# esp32_wheel_robot.net
KiCad netlist of a schematic drawn in EasyEDA Pro
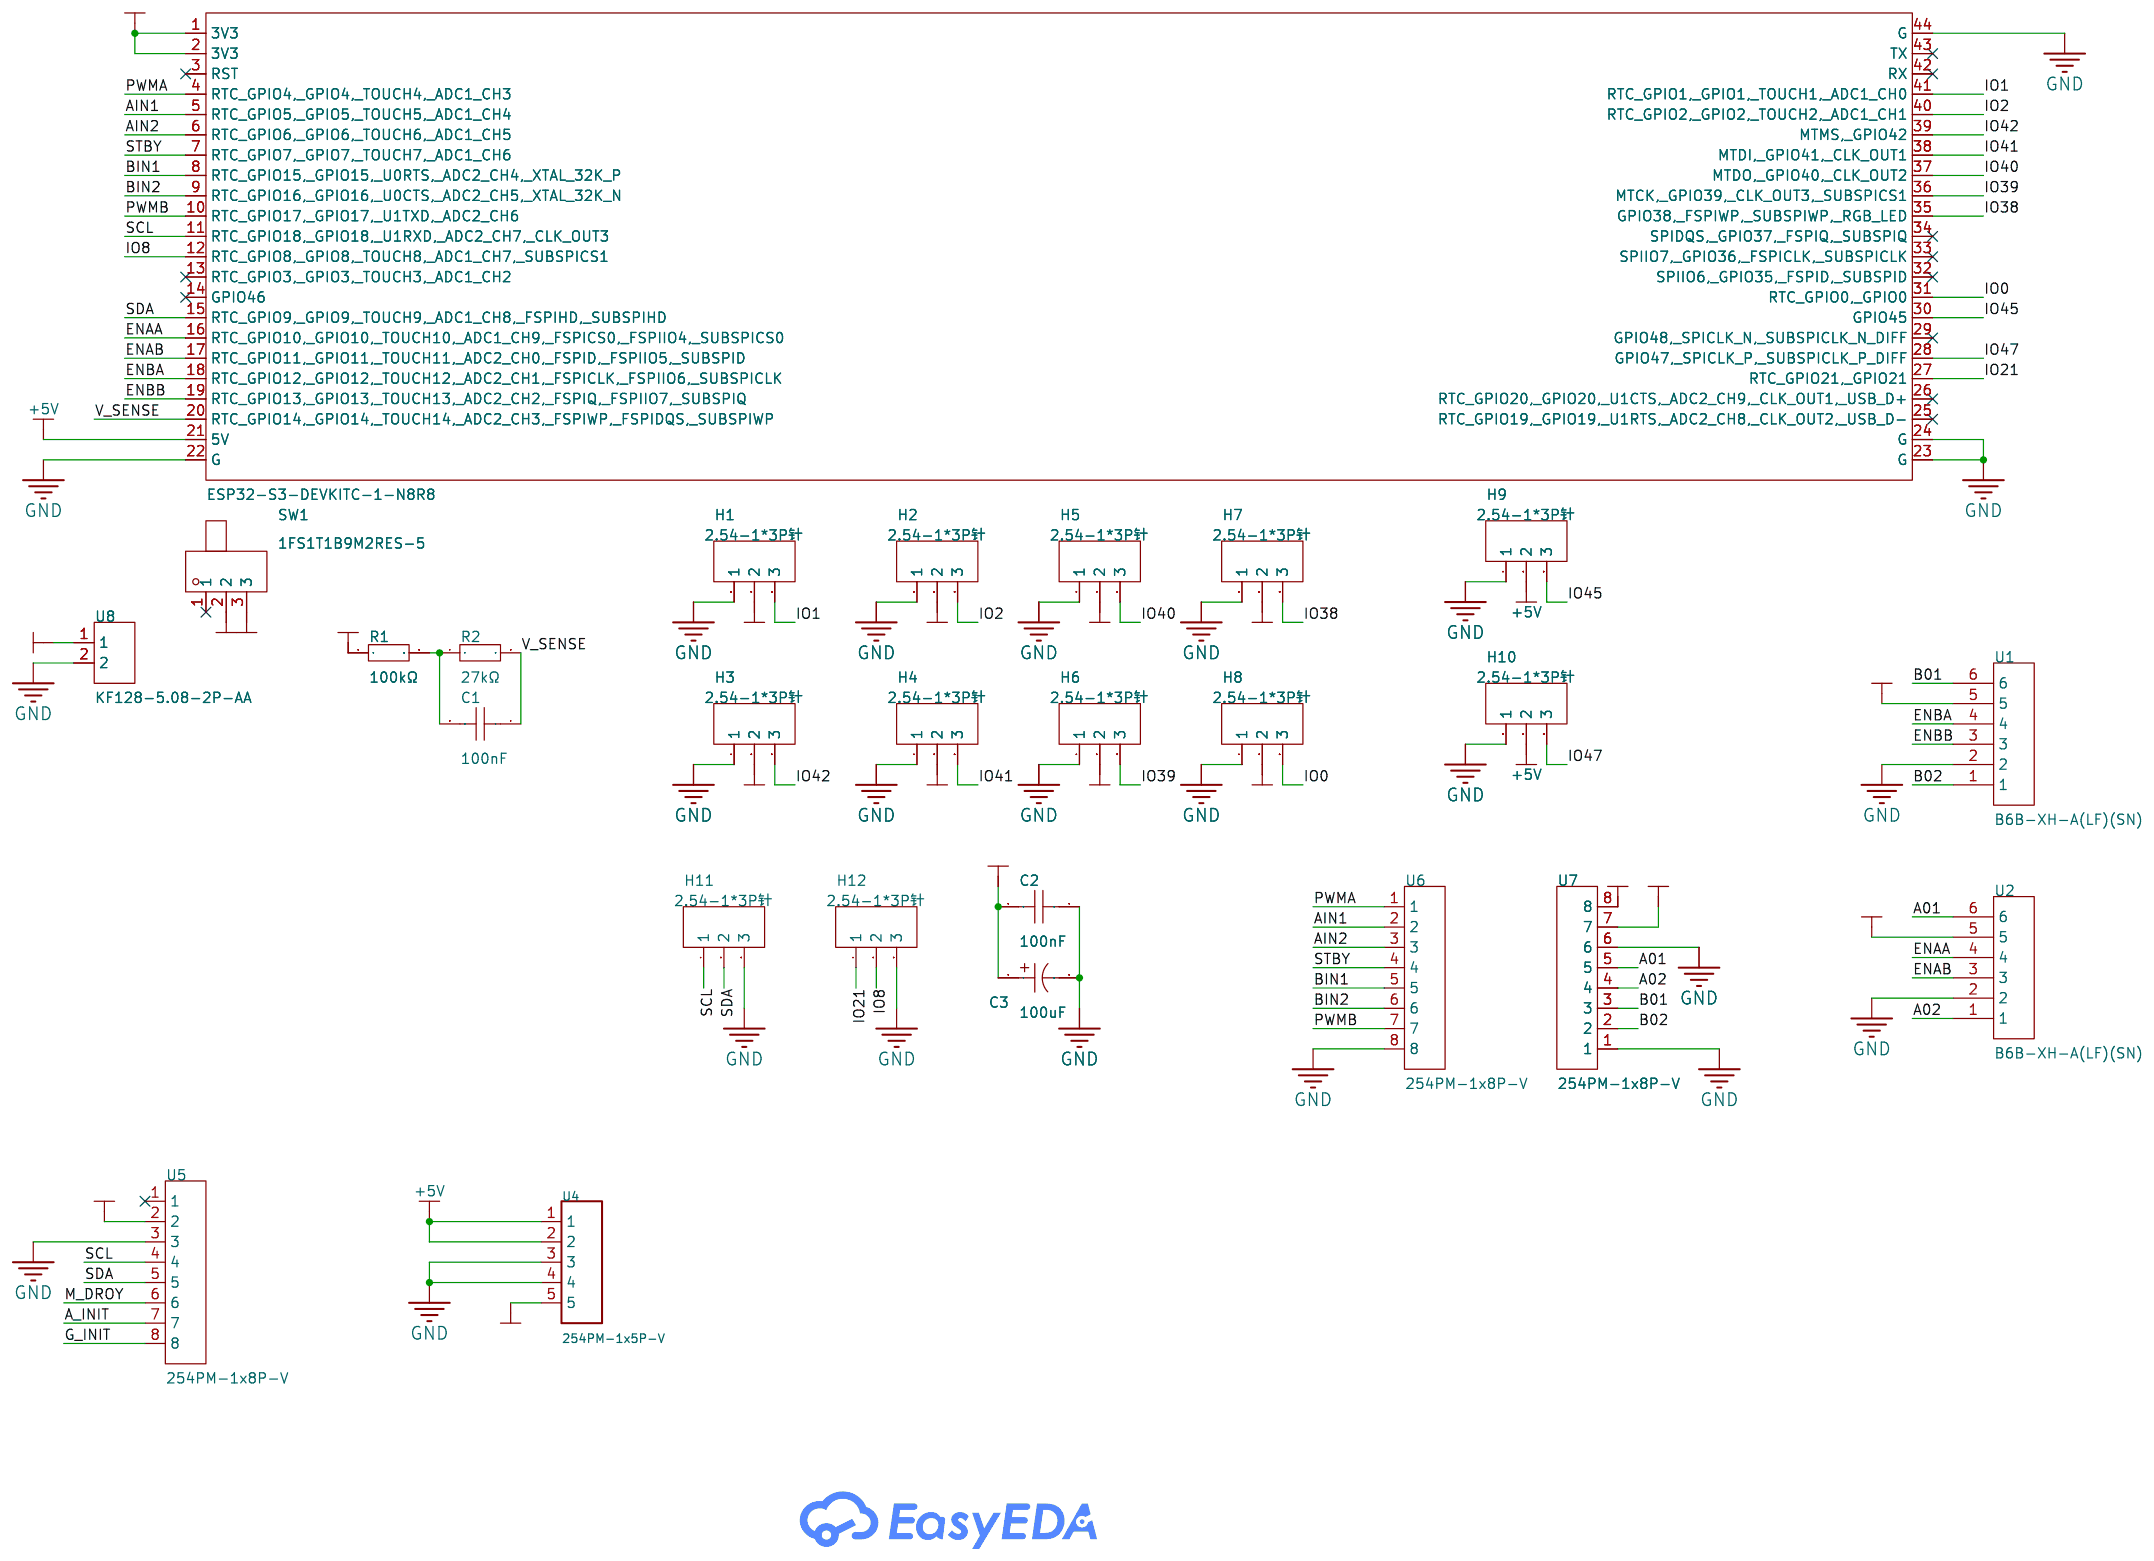
[diagram p0: schematic sheet]

(export (version "E")
  (design (tool "Eeschema 10.0.6"))
  (components
    (comp (ref "C1")
      (value "100nF")
      (footprint "easyedapro:C0603")
      (fields
        (field (name "Manufacturer Part") "CC1H104MC1FD3F6C10MF")
        (field (name "Manufacturer") "Dersonic(德尔创)")
      )
      (libsource (lib "easyedapro") (part "CAP_OLD"))
    )
    (comp (ref "C2")
      (value "100nF")
      (footprint "easyedapro:C0603")
      (fields
        (field (name "Manufacturer Part") "CC1H104MC1FD3F6C10MF")
        (field (name "Manufacturer") "Dersonic(德尔创)")
      )
      (libsource (lib "easyedapro") (part "CAP_OLD"))
    )
    (comp (ref "C3")
      (value "100uF")
      (footprint "easyedapro:CAP-TH_BD10.0-P5.00-D0.8-FD_UKZ1E101MPM1TD")
      (fields
        (field (name "Manufacturer Part") "UKZ1E101MPM1TD")
        (field (name "Manufacturer") "Nichicon(尼吉康)")
      )
      (libsource (lib "easyedapro") (part "UKZ1E101MPM1TD"))
    )
    (comp (ref "H1")
      (value "2.54-1*3P针")
      (footprint "easyedapro:HDR-TH_3P-P2.54-V-M-1")
      (fields (field (name "Manufacturer") "BOOMELE(博穆精密)"))
      (libsource (lib "easyedapro") (part "Header-Male-2.54_1x3"))
    )
    (comp (ref "H2")
      (value "2.54-1*3P针")
      (footprint "easyedapro:HDR-TH_3P-P2.54-V-M-1")
      (fields (field (name "Manufacturer") "BOOMELE(博穆精密)"))
      (libsource (lib "easyedapro") (part "Header-Male-2.54_1x3"))
    )
    (comp (ref "H3")
      (value "2.54-1*3P针")
      (footprint "easyedapro:HDR-TH_3P-P2.54-V-M-1")
      (fields (field (name "Manufacturer") "BOOMELE(博穆精密)"))
      (libsource (lib "easyedapro") (part "Header-Male-2.54_1x3"))
    )
    (comp (ref "H4")
      (value "2.54-1*3P针")
      (footprint "easyedapro:HDR-TH_3P-P2.54-V-M-1")
      (fields (field (name "Manufacturer") "BOOMELE(博穆精密)"))
      (libsource (lib "easyedapro") (part "Header-Male-2.54_1x3"))
    )
    (comp (ref "H5")
      (value "2.54-1*3P针")
      (footprint "easyedapro:HDR-TH_3P-P2.54-V-M-1")
      (fields (field (name "Manufacturer") "BOOMELE(博穆精密)"))
      (libsource (lib "easyedapro") (part "Header-Male-2.54_1x3"))
    )
    (comp (ref "H6")
      (value "2.54-1*3P针")
      (footprint "easyedapro:HDR-TH_3P-P2.54-V-M-1")
      (fields (field (name "Manufacturer") "BOOMELE(博穆精密)"))
      (libsource (lib "easyedapro") (part "Header-Male-2.54_1x3"))
    )
    (comp (ref "H7")
      (value "2.54-1*3P针")
      (footprint "easyedapro:HDR-TH_3P-P2.54-V-M-1")
      (fields (field (name "Manufacturer") "BOOMELE(博穆精密)"))
      (libsource (lib "easyedapro") (part "Header-Male-2.54_1x3"))
    )
    (comp (ref "H8")
      (value "2.54-1*3P针")
      (footprint "easyedapro:HDR-TH_3P-P2.54-V-M-1")
      (fields (field (name "Manufacturer") "BOOMELE(博穆精密)"))
      (libsource (lib "easyedapro") (part "Header-Male-2.54_1x3"))
    )
    (comp (ref "H9")
      (value "2.54-1*3P针")
      (footprint "easyedapro:HDR-TH_3P-P2.54-V-M-1")
      (fields (field (name "Manufacturer") "BOOMELE(博穆精密)"))
      (libsource (lib "easyedapro") (part "Header-Male-2.54_1x3"))
    )
    (comp (ref "H10")
      (value "2.54-1*3P针")
      (footprint "easyedapro:HDR-TH_3P-P2.54-V-M-1")
      (fields (field (name "Manufacturer") "BOOMELE(博穆精密)"))
      (libsource (lib "easyedapro") (part "Header-Male-2.54_1x3"))
    )
    (comp (ref "H11")
      (value "2.54-1*3P针")
      (footprint "easyedapro:HDR-TH_3P-P2.54-V-M-1")
      (fields (field (name "Manufacturer") "BOOMELE(博穆精密)"))
      (libsource (lib "easyedapro") (part "Header-Male-2.54_1x3"))
    )
    (comp (ref "H12")
      (value "2.54-1*3P针")
      (footprint "easyedapro:HDR-TH_3P-P2.54-V-M-1")
      (fields (field (name "Manufacturer") "BOOMELE(博穆精密)"))
      (libsource (lib "easyedapro") (part "Header-Male-2.54_1x3"))
    )
    (comp (ref "R1")
      (value "100kΩ")
      (footprint "easyedapro:R0603")
      (fields
        (field (name "Manufacturer Part") "MF1/4W-100KΩ±1% T")
        (field (name "Manufacturer") "CCO(千志电子)")
      )
      (libsource (lib "easyedapro") (part "Res"))
    )
    (comp (ref "R2")
      (value "27kΩ")
      (footprint "easyedapro:R0603")
      (fields (field (name "Manufacturer Part") "MF1/4W-27KΩ±1% T") (field (name "Manufacturer") "CCO(千志电子)"))
      (libsource (lib "easyedapro") (part "Res"))
    )
    (comp (ref "SW1")
      (value "1FS1T1B9M2RES-5")
      (footprint "easyedapro:SW-TH_1FS1T1B9M2RES-5")
      (fields (field (name "Manufacturer") "Dailywell(德利威)"))
      (libsource (lib "easyedapro") (part "1FS1T1B9M2RES-5"))
    )
    (comp (ref "U1")
      (value "B6B-XH-A(LF)(SN)")
      (footprint "easyedapro:CONN-TH_6P-P2.50_B6B-XH-A-LF-SN")
      (fields (field (name "Manufacturer") "JST"))
      (libsource (lib "easyedapro") (part "B6B-XH-A(LF)(SN)"))
    )
    (comp (ref "U2")
      (value "B6B-XH-A(LF)(SN)")
      (footprint "easyedapro:CONN-TH_6P-P2.50_B6B-XH-A-LF-SN")
      (fields (field (name "Manufacturer") "JST"))
      (libsource (lib "easyedapro") (part "B6B-XH-A(LF)(SN)"))
    )
    (comp (ref "U3")
      (value "ESP32-S3-DEVKITC-1-N8R8")
      (footprint "easyedapro:CONN-TH_ESP32-S3-DEVKITC-1U-N8")
      (fields (field (name "Manufacturer") "ESPRESSIF(乐鑫)"))
      (libsource (lib "easyedapro") (part "ESP32-S3-DEVKITC-1-N8R8"))
    )
    (comp (ref "U4")
      (value "254PM-1x5P-V")
      (footprint "easyedapro:HDR-TH_5P-P2.54-V-F-3")
      (fields (field (name "Manufacturer") "LXWCONN(连兴旺电子)"))
      (libsource (lib "easyedapro") (part "254PM-1X5P-V"))
    )
    (comp (ref "U5")
      (value "254PM-1x8P-V")
      (footprint "easyedapro:HDR-TH_8P-P2.54-V-F_5")
      (fields (field (name "Manufacturer") "LXWCONN(连兴旺电子)"))
      (libsource (lib "easyedapro") (part "254PM-1X8P-V"))
    )
    (comp (ref "U6")
      (value "254PM-1x8P-V")
      (footprint "easyedapro:HDR-TH_8P-P2.54-V-F_5")
      (fields (field (name "Manufacturer") "LXWCONN(连兴旺电子)"))
      (libsource (lib "easyedapro") (part "254PM-1X8P-V"))
    )
    (comp (ref "U7")
      (value "254PM-1x8P-V")
      (footprint "easyedapro:HDR-TH_8P-P2.54-V-F_5")
      (fields (field (name "Manufacturer") "LXWCONN(连兴旺电子)"))
      (libsource (lib "easyedapro") (part "254PM-1X8P-V"))
    )
    (comp (ref "U8")
      (value "KF128-5.08-2P-AA")
      (footprint "easyedapro:CONN-TH_P5.08_KF128-5.08-2P")
      (fields (field (name "Manufacturer") "KEFA(科发)"))
      (libsource (lib "easyedapro") (part "KF128-5.08-2P"))
    )
  )
  (nets
    (net (code "1") (name "+3V3") (class "Default")
      (node (ref "H1") (pin "2") (pinfunction "2_2") (pintype "input"))
      (node (ref "H2") (pin "2") (pinfunction "2_2") (pintype "input"))
      (node (ref "H3") (pin "2") (pinfunction "2_2") (pintype "input"))
      (node (ref "H4") (pin "2") (pinfunction "2_2") (pintype "input"))
      (node (ref "H5") (pin "2") (pinfunction "2_2") (pintype "input"))
      (node (ref "H6") (pin "2") (pinfunction "2_2") (pintype "input"))
      (node (ref "H7") (pin "2") (pinfunction "2_2") (pintype "input"))
      (node (ref "H8") (pin "2") (pinfunction "2_2") (pintype "input"))
      (node (ref "U1") (pin "5") (pinfunction "5_5") (pintype "unspecified"))
      (node (ref "U2") (pin "5") (pinfunction "5_5") (pintype "unspecified"))
      (node (ref "U3") (pin "1") (pinfunction "3V3_1") (pintype "unspecified"))
      (node (ref "U3") (pin "2") (pinfunction "3V3_2") (pintype "unspecified"))
      (node (ref "U5") (pin "2") (pinfunction "2_2") (pintype "unspecified"))
      (node (ref "U7") (pin "7") (pinfunction "7_7") (pintype "unspecified"))
    )
    (net (code "2") (name "+5V") (class "Default")
      (node (ref "H10") (pin "2") (pinfunction "2_2") (pintype "input"))
      (node (ref "H9") (pin "2") (pinfunction "2_2") (pintype "input"))
      (node (ref "U3") (pin "21") (pinfunction "5V_21") (pintype "unspecified"))
      (node (ref "U4") (pin "1") (pinfunction "1_1") (pintype "unspecified"))
      (node (ref "U4") (pin "2") (pinfunction "2_2") (pintype "unspecified"))
    )
    (net (code "3") (name "/A01") (class "Default")
      (node (ref "U2") (pin "6") (pinfunction "6_6") (pintype "unspecified"))
      (node (ref "U7") (pin "5") (pinfunction "5_5") (pintype "unspecified"))
    )
    (net (code "4") (name "/A02") (class "Default")
      (node (ref "U2") (pin "1") (pinfunction "1_1") (pintype "unspecified"))
      (node (ref "U7") (pin "4") (pinfunction "4_4") (pintype "unspecified"))
    )
    (net (code "5") (name "/AIN1") (class "Default")
      (node (ref "U3") (pin "5") (pinfunction "RTC_GPIO5,_GPIO5,_TOUCH5,_ADC1_CH4_5") (pintype "unspecified"))
      (node (ref "U6") (pin "2") (pinfunction "2_2") (pintype "unspecified"))
    )
    (net (code "6") (name "/AIN2") (class "Default")
      (node (ref "U3") (pin "6") (pinfunction "RTC_GPIO6,_GPIO6,_TOUCH6,_ADC1_CH5_6") (pintype "unspecified"))
      (node (ref "U6") (pin "3") (pinfunction "3_3") (pintype "unspecified"))
    )
    (net (code "7") (name "/A_INIT") (class "Default")
      (node (ref "U5") (pin "7") (pinfunction "7_7") (pintype "unspecified"))
    )
    (net (code "8") (name "/B01") (class "Default")
      (node (ref "U1") (pin "6") (pinfunction "6_6") (pintype "unspecified"))
      (node (ref "U7") (pin "3") (pinfunction "3_3") (pintype "unspecified"))
    )
    (net (code "9") (name "/B02") (class "Default")
      (node (ref "U1") (pin "1") (pinfunction "1_1") (pintype "unspecified"))
      (node (ref "U7") (pin "2") (pinfunction "2_2") (pintype "unspecified"))
    )
    (net (code "10") (name "/BIN1") (class "Default")
      (node (ref "U3") (pin "8") (pinfunction "RTC_GPIO15,_GPIO15,_U0RTS,_ADC2_CH4,_XTAL_32K_P_8") (pintype "unspecified"))
      (node (ref "U6") (pin "5") (pinfunction "5_5") (pintype "unspecified"))
    )
    (net (code "11") (name "/BIN2") (class "Default")
      (node (ref "U3") (pin "9") (pinfunction "RTC_GPIO16,_GPIO16,_U0CTS,_ADC2_CH5,_XTAL_32K_N_9") (pintype "unspecified"))
      (node (ref "U6") (pin "6") (pinfunction "6_6") (pintype "unspecified"))
    )
    (net (code "12") (name "/ENAA") (class "Default")
      (node (ref "U2") (pin "4") (pinfunction "4_4") (pintype "unspecified"))
      (node (ref "U3") (pin "16") (pinfunction "RTC_GPIO10,_GPIO10,_TOUCH10,_ADC1_CH9,_FSPICS0,_FSPIIO4,_SUBSPICS0_16") (pintype "unspecified"))
    )
    (net (code "13") (name "/ENAB") (class "Default")
      (node (ref "U2") (pin "3") (pinfunction "3_3") (pintype "unspecified"))
      (node (ref "U3") (pin "17") (pinfunction "RTC_GPIO11,_GPIO11,_TOUCH11,_ADC2_CH0,_FSPID,_FSPIIO5,_SUBSPID_17") (pintype "unspecified"))
    )
    (net (code "14") (name "/ENBA") (class "Default")
      (node (ref "U1") (pin "4") (pinfunction "4_4") (pintype "unspecified"))
      (node (ref "U3") (pin "18") (pinfunction "RTC_GPIO12,_GPIO12,_TOUCH12,_ADC2_CH1,_FSPICLK,_FSPIIO6,_SUBSPICLK_18") (pintype "unspecified"))
    )
    (net (code "15") (name "/ENBB") (class "Default")
      (node (ref "U1") (pin "3") (pinfunction "3_3") (pintype "unspecified"))
      (node (ref "U3") (pin "19") (pinfunction "RTC_GPIO13,_GPIO13,_TOUCH13,_ADC2_CH2,_FSPIQ,_FSPIIO7,_SUBSPIQ_19") (pintype "unspecified"))
    )
    (net (code "16") (name "/G_INIT") (class "Default")
      (node (ref "U5") (pin "8") (pinfunction "8_8") (pintype "unspecified"))
    )
    (net (code "17") (name "/IO0") (class "Default")
      (node (ref "H8") (pin "3") (pinfunction "3_3") (pintype "input"))
      (node (ref "U3") (pin "31") (pinfunction "RTC_GPIO0,_GPIO0_31") (pintype "unspecified"))
    )
    (net (code "18") (name "/IO1") (class "Default")
      (node (ref "H1") (pin "3") (pinfunction "3_3") (pintype "input"))
      (node (ref "U3") (pin "41") (pinfunction "RTC_GPIO1,_GPIO1,_TOUCH1,_ADC1_CH0_41") (pintype "unspecified"))
    )
    (net (code "19") (name "/IO2") (class "Default")
      (node (ref "H2") (pin "3") (pinfunction "3_3") (pintype "input"))
      (node (ref "U3") (pin "40") (pinfunction "RTC_GPIO2,_GPIO2,_TOUCH2,_ADC1_CH1_40") (pintype "unspecified"))
    )
    (net (code "20") (name "/IO8") (class "Default")
      (node (ref "H12") (pin "2") (pinfunction "2_2") (pintype "input"))
      (node (ref "U3") (pin "12") (pinfunction "RTC_GPIO8,_GPIO8,_TOUCH8,_ADC1_CH7,_SUBSPICS1_12") (pintype "unspecified"))
    )
    (net (code "21") (name "/IO21") (class "Default")
      (node (ref "H12") (pin "1") (pinfunction "1_1") (pintype "input"))
      (node (ref "U3") (pin "27") (pinfunction "RTC_GPIO21,_GPIO21_27") (pintype "unspecified"))
    )
    (net (code "22") (name "/IO38") (class "Default")
      (node (ref "H7") (pin "3") (pinfunction "3_3") (pintype "input"))
      (node (ref "U3") (pin "35") (pinfunction "GPIO38,_FSPIWP,_SUBSPIWP,_RGB_LED_35") (pintype "unspecified"))
    )
    (net (code "23") (name "/IO39") (class "Default")
      (node (ref "H6") (pin "3") (pinfunction "3_3") (pintype "input"))
      (node (ref "U3") (pin "36") (pinfunction "MTCK,_GPIO39,_CLK_OUT3,_SUBSPICS1_36") (pintype "unspecified"))
    )
    (net (code "24") (name "/IO40") (class "Default")
      (node (ref "H5") (pin "3") (pinfunction "3_3") (pintype "input"))
      (node (ref "U3") (pin "37") (pinfunction "MTDO,_GPIO40,_CLK_OUT2_37") (pintype "unspecified"))
    )
    (net (code "25") (name "/IO41") (class "Default")
      (node (ref "H4") (pin "3") (pinfunction "3_3") (pintype "input"))
      (node (ref "U3") (pin "38") (pinfunction "MTDI,_GPIO41,_CLK_OUT1_38") (pintype "unspecified"))
    )
    (net (code "26") (name "/IO42") (class "Default")
      (node (ref "H3") (pin "3") (pinfunction "3_3") (pintype "input"))
      (node (ref "U3") (pin "39") (pinfunction "MTMS,_GPIO42_39") (pintype "unspecified"))
    )
    (net (code "27") (name "/IO45") (class "Default")
      (node (ref "H9") (pin "3") (pinfunction "3_3") (pintype "input"))
      (node (ref "U3") (pin "30") (pinfunction "GPIO45_30") (pintype "unspecified"))
    )
    (net (code "28") (name "/IO47") (class "Default")
      (node (ref "H10") (pin "3") (pinfunction "3_3") (pintype "input"))
      (node (ref "U3") (pin "28") (pinfunction "GPIO47,_SPICLK_P,_SUBSPICLK_P_DIFF_28") (pintype "unspecified"))
    )
    (net (code "29") (name "/M_DROY") (class "Default")
      (node (ref "U5") (pin "6") (pinfunction "6_6") (pintype "unspecified"))
    )
    (net (code "30") (name "/PWMA") (class "Default")
      (node (ref "U3") (pin "4") (pinfunction "RTC_GPIO4,_GPIO4,_TOUCH4,_ADC1_CH3_4") (pintype "unspecified"))
      (node (ref "U6") (pin "1") (pinfunction "1_1") (pintype "unspecified"))
    )
    (net (code "31") (name "/PWMB") (class "Default")
      (node (ref "U3") (pin "10") (pinfunction "RTC_GPIO17,_GPIO17,_U1TXD,_ADC2_CH6_10") (pintype "unspecified"))
      (node (ref "U6") (pin "7") (pinfunction "7_7") (pintype "unspecified"))
    )
    (net (code "32") (name "/SCL") (class "Default")
      (node (ref "H11") (pin "1") (pinfunction "1_1") (pintype "input"))
      (node (ref "U3") (pin "11") (pinfunction "RTC_GPIO18,_GPIO18,_U1RXD,_ADC2_CH7,_CLK_OUT3_11") (pintype "unspecified"))
      (node (ref "U5") (pin "4") (pinfunction "4_4") (pintype "unspecified"))
    )
    (net (code "33") (name "/SDA") (class "Default")
      (node (ref "H11") (pin "2") (pinfunction "2_2") (pintype "input"))
      (node (ref "U3") (pin "15") (pinfunction "RTC_GPIO9,_GPIO9,_TOUCH9,_ADC1_CH8,_FSPIHD,_SUBSPIHD_15") (pintype "unspecified"))
      (node (ref "U5") (pin "5") (pinfunction "5_5") (pintype "unspecified"))
    )
    (net (code "34") (name "/STBY") (class "Default")
      (node (ref "U3") (pin "7") (pinfunction "RTC_GPIO7,_GPIO7,_TOUCH7,_ADC1_CH6_7") (pintype "unspecified"))
      (node (ref "U6") (pin "4") (pinfunction "4_4") (pintype "unspecified"))
    )
    (net (code "35") (name "/V_SENSE") (class "Default")
      (node (ref "C1") (pin "1") (pinfunction "1_1") (pintype "input"))
      (node (ref "R2") (pin "2") (pinfunction "2_2") (pintype "input"))
      (node (ref "U3") (pin "20") (pinfunction "RTC_GPIO14,_GPIO14,_TOUCH14,_ADC2_CH3,_FSPIWP,_FSPIDQS,_SUBSPIWP_20") (pintype "unspecified"))
    )
    (net (code "36") (name "12V") (class "Default")
      (node (ref "SW1") (pin "2") (pinfunction "2_2") (pintype "unspecified"))
      (node (ref "U8") (pin "1") (pinfunction "1_1") (pintype "unspecified"))
    )
    (net (code "37") (name "GND") (class "Default")
      (node (ref "C2") (pin "1") (pinfunction "1_1") (pintype "input"))
      (node (ref "C3") (pin "2") (pinfunction "2_2") (pintype "input"))
      (node (ref "H1") (pin "1") (pinfunction "1_1") (pintype "input"))
      (node (ref "H10") (pin "1") (pinfunction "1_1") (pintype "input"))
      (node (ref "H11") (pin "3") (pinfunction "3_3") (pintype "input"))
      (node (ref "H12") (pin "3") (pinfunction "3_3") (pintype "input"))
      (node (ref "H2") (pin "1") (pinfunction "1_1") (pintype "input"))
      (node (ref "H3") (pin "1") (pinfunction "1_1") (pintype "input"))
      (node (ref "H4") (pin "1") (pinfunction "1_1") (pintype "input"))
      (node (ref "H5") (pin "1") (pinfunction "1_1") (pintype "input"))
      (node (ref "H6") (pin "1") (pinfunction "1_1") (pintype "input"))
      (node (ref "H7") (pin "1") (pinfunction "1_1") (pintype "input"))
      (node (ref "H8") (pin "1") (pinfunction "1_1") (pintype "input"))
      (node (ref "H9") (pin "1") (pinfunction "1_1") (pintype "input"))
      (node (ref "U1") (pin "2") (pinfunction "2_2") (pintype "unspecified"))
      (node (ref "U2") (pin "2") (pinfunction "2_2") (pintype "unspecified"))
      (node (ref "U3") (pin "22") (pinfunction "G_22") (pintype "unspecified"))
      (node (ref "U3") (pin "23") (pinfunction "G_23") (pintype "unspecified"))
      (node (ref "U3") (pin "24") (pinfunction "G_24") (pintype "unspecified"))
      (node (ref "U3") (pin "44") (pinfunction "G_44") (pintype "unspecified"))
      (node (ref "U4") (pin "3") (pinfunction "3_3") (pintype "unspecified"))
      (node (ref "U4") (pin "4") (pinfunction "4_4") (pintype "unspecified"))
      (node (ref "U5") (pin "3") (pinfunction "3_3") (pintype "unspecified"))
      (node (ref "U6") (pin "8") (pinfunction "8_8") (pintype "unspecified"))
      (node (ref "U7") (pin "1") (pinfunction "1_1") (pintype "unspecified"))
      (node (ref "U7") (pin "6") (pinfunction "6_6") (pintype "unspecified"))
      (node (ref "U8") (pin "2") (pinfunction "2_2") (pintype "unspecified"))
    )
    (net (code "38") (name "Net-(C1-Pad2)") (class "Default")
      (node (ref "C1") (pin "2") (pinfunction "2_2") (pintype "input"))
      (node (ref "R1") (pin "2") (pinfunction "2_2") (pintype "input"))
      (node (ref "R2") (pin "1") (pinfunction "1_1") (pintype "input"))
    )
    (net (code "39") (name "VM") (class "Default")
      (node (ref "C2") (pin "2") (pinfunction "2_2") (pintype "input"))
      (node (ref "C3") (pin "1") (pinfunction "1_1") (pintype "input"))
      (node (ref "R1") (pin "1") (pinfunction "1_1") (pintype "input"))
      (node (ref "SW1") (pin "3") (pinfunction "3_3") (pintype "unspecified"))
      (node (ref "U4") (pin "5") (pinfunction "5_5") (pintype "unspecified"))
      (node (ref "U7") (pin "8") (pinfunction "8_8") (pintype "unspecified"))
    )
    (net (code "40") (name "unconnected-(SW1-Pad1)") (class "Default")
      (node (ref "SW1") (pin "1") (pinfunction "1_1") (pintype "unspecified+no_connect"))
    )
    (net (code "41") (name "unconnected-(U3-GPIO46-Pad14)") (class "Default")
      (node (ref "U3") (pin "14") (pinfunction "GPIO46_14") (pintype "unspecified+no_connect"))
    )
    (net (code "42") (name "unconnected-(U3-GPIO48,_SPICLK_N,_SUBSPICLK_N_DIFF-Pad29)") (class "Default")
      (node (ref "U3") (pin "29") (pinfunction "GPIO48,_SPICLK_N,_SUBSPICLK_N_DIFF_29") (pintype "unspecified+no_connect"))
    )
    (net (code "43") (name "unconnected-(U3-RST-Pad3)") (class "Default")
      (node (ref "U3") (pin "3") (pinfunction "RST_3") (pintype "unspecified+no_connect"))
    )
    (net (code "44") (name "unconnected-(U3-RTC_GPIO3,_GPIO3,_TOUCH3,_ADC1_CH2-Pad13)") (class "Default")
      (node (ref "U3") (pin "13") (pinfunction "RTC_GPIO3,_GPIO3,_TOUCH3,_ADC1_CH2_13") (pintype "unspecified+no_connect"))
    )
    (net (code "45") (name "unconnected-(U3-RTC_GPIO19,_GPIO19,_U1RTS,_ADC2_CH8,_CLK_OUT2,_USB_D--Pad25)") (class "Default")
      (node (ref "U3") (pin "25") (pinfunction "RTC_GPIO19,_GPIO19,_U1RTS,_ADC2_CH8,_CLK_OUT2,_USB_D-_25") (pintype "unspecified+no_connect"))
    )
    (net (code "46") (name "unconnected-(U3-RTC_GPIO20,_GPIO20,_U1CTS,_ADC2_CH9,_CLK_OUT1,_USB_D+-Pad26)") (class "Default")
      (node (ref "U3") (pin "26") (pinfunction "RTC_GPIO20,_GPIO20,_U1CTS,_ADC2_CH9,_CLK_OUT1,_USB_D+_26") (pintype "unspecified+no_connect"))
    )
    (net (code "47") (name "unconnected-(U3-RX-Pad42)") (class "Default")
      (node (ref "U3") (pin "42") (pinfunction "RX_42") (pintype "unspecified+no_connect"))
    )
    (net (code "48") (name "unconnected-(U3-SPIDQS,_GPIO37,_FSPIQ,_SUBSPIQ-Pad34)") (class "Default")
      (node (ref "U3") (pin "34") (pinfunction "SPIDQS,_GPIO37,_FSPIQ,_SUBSPIQ_34") (pintype "unspecified+no_connect"))
    )
    (net (code "49") (name "unconnected-(U3-SPIIO6,_GPIO35,_FSPID,_SUBSPID-Pad32)") (class "Default")
      (node (ref "U3") (pin "32") (pinfunction "SPIIO6,_GPIO35,_FSPID,_SUBSPID_32") (pintype "unspecified+no_connect"))
    )
    (net (code "50") (name "unconnected-(U3-SPIIO7,_GPIO36,_FSPICLK,_SUBSPICLK-Pad33)") (class "Default")
      (node (ref "U3") (pin "33") (pinfunction "SPIIO7,_GPIO36,_FSPICLK,_SUBSPICLK_33") (pintype "unspecified+no_connect"))
    )
    (net (code "51") (name "unconnected-(U3-TX-Pad43)") (class "Default")
      (node (ref "U3") (pin "43") (pinfunction "TX_43") (pintype "unspecified+no_connect"))
    )
    (net (code "52") (name "unconnected-(U5-Pad1)") (class "Default")
      (node (ref "U5") (pin "1") (pinfunction "1_1") (pintype "unspecified+no_connect"))
    )
  )
)
